# nguyenly.net
KiCad netlist of a schematic drawn in Altium Designer
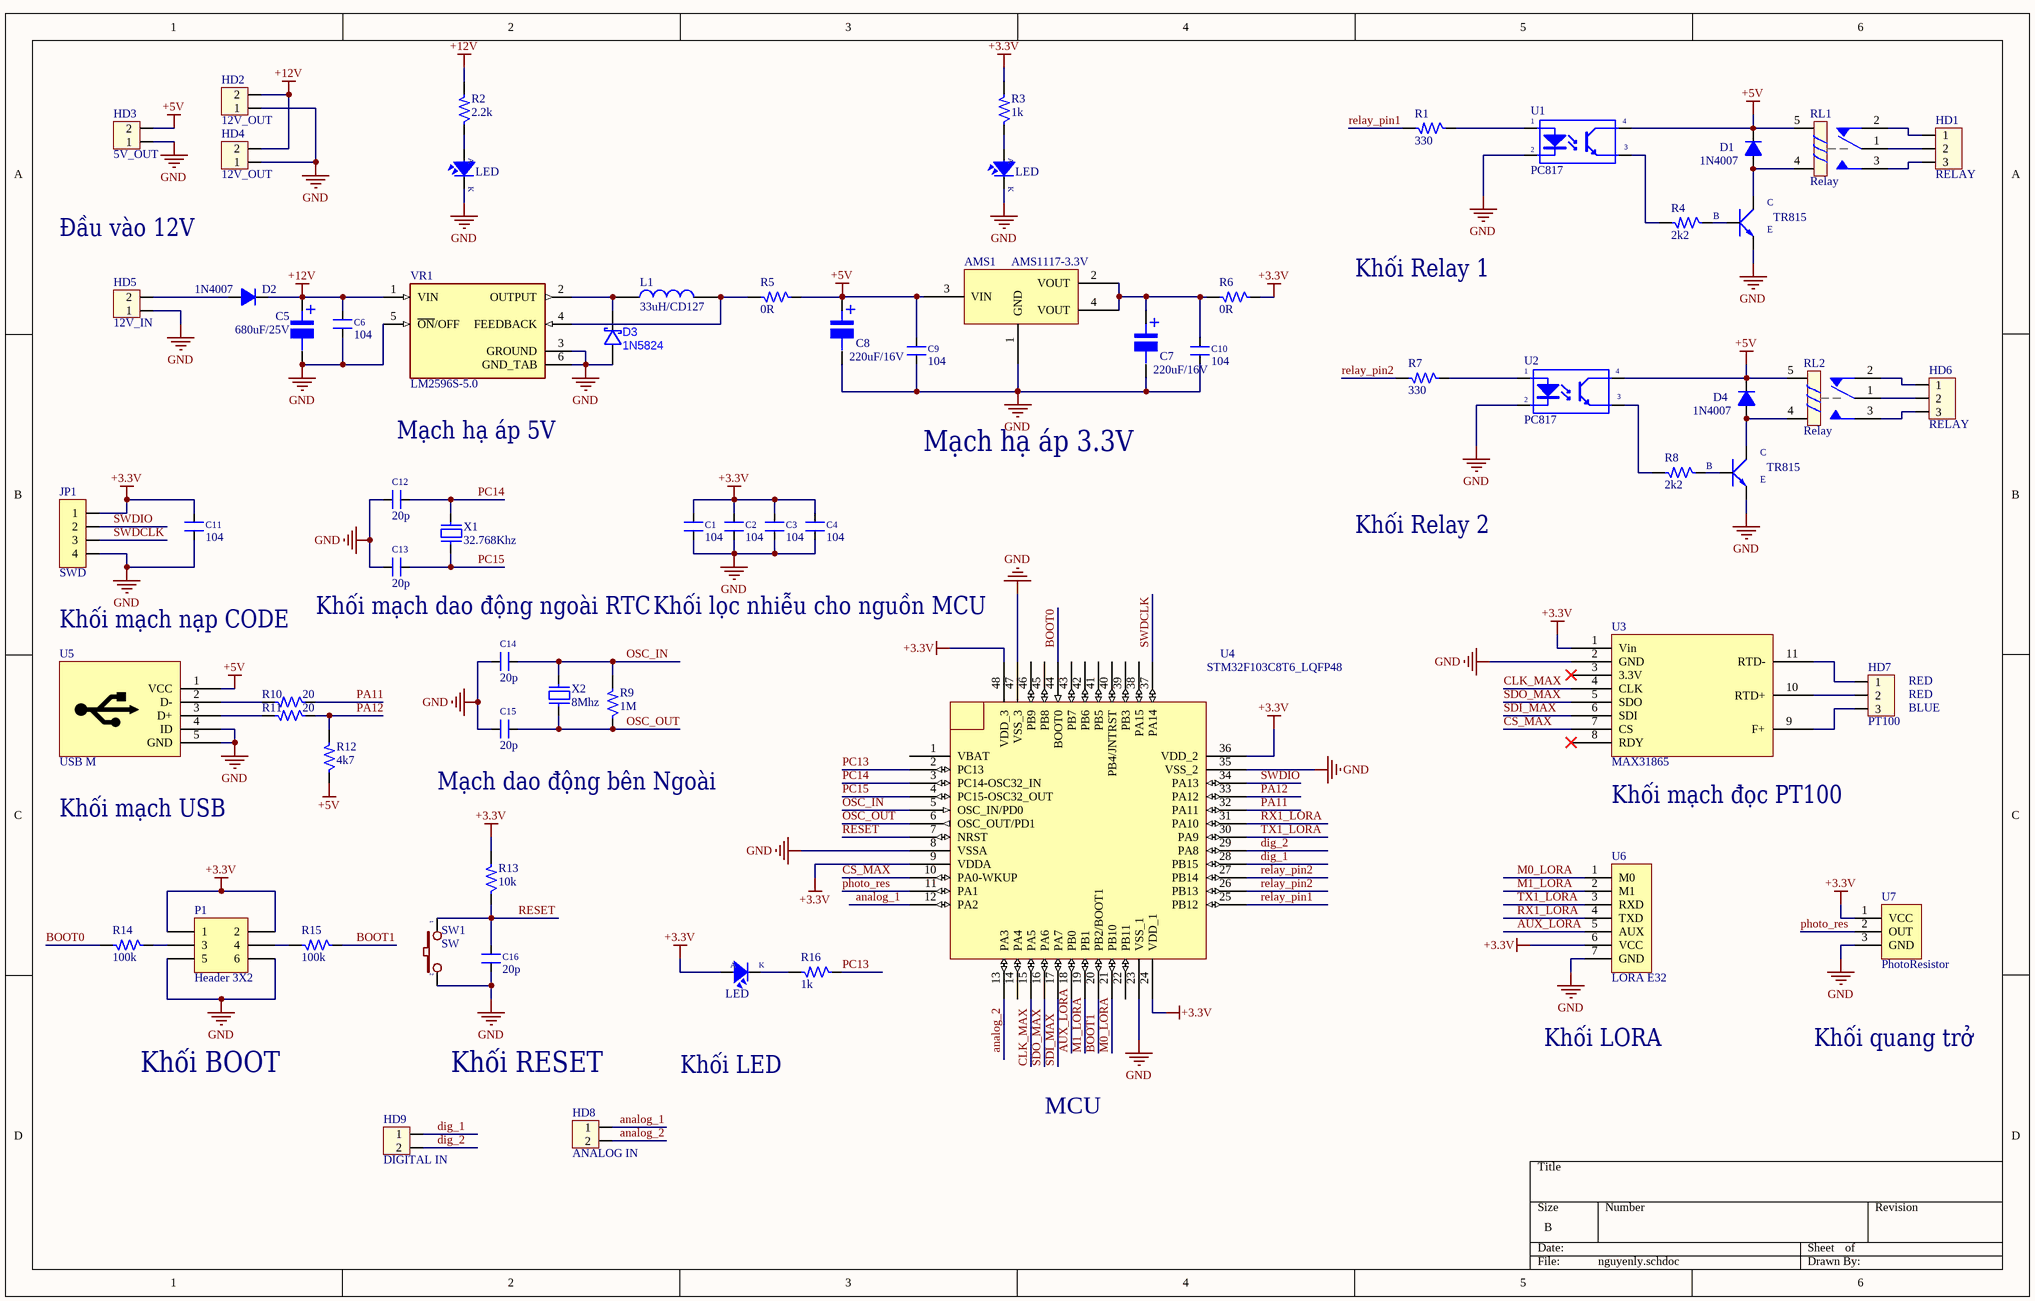
[diagram p0: nguyenly.schdoc]

(export (version "E")
  (design (tool "Eeschema 10.0.6"))
  (components
    (comp (ref "AMS1")
      (value "AMS1117-3.3V")
      (footprint "SOT223")
      (description "thegioiic. Dán (SOT-223)")
      (libsource (lib "Altium_Lib_by_KhueNguyenCreator") (part "AMS1117 SMD"))
    )
    (comp (ref "C1")
      (value "104")
      (footprint "SM-CAP-0805")
      (fields (field (name "DESIGNED BY") "VanDungEvn"))
      (libsource (lib "My library altium") (part "CAP SMD"))
    )
    (comp (ref "C2")
      (value "104")
      (footprint "SM-CAP-0805")
      (fields (field (name "DESIGNED BY") "VanDungEvn"))
      (libsource (lib "My library altium") (part "CAP SMD"))
    )
    (comp (ref "C3")
      (value "104")
      (footprint "SM-CAP-0805")
      (fields (field (name "DESIGNED BY") "VanDungEvn"))
      (libsource (lib "My library altium") (part "CAP SMD"))
    )
    (comp (ref "C4")
      (value "104")
      (footprint "SM-CAP-0805")
      (fields (field (name "DESIGNED BY") "VanDungEvn"))
      (libsource (lib "My library altium") (part "CAP SMD"))
    )
    (comp (ref "C5")
      (value "680uF/25V")
      (footprint "tu nhom 10 (G)")
      (description "Dán. Mua ở thegioiic")
      (libsource (lib "Altium_Lib_by_KhueNguyenCreator") (part "Tu Nhom 220uF 25V"))
    )
    (comp (ref "C6")
      (value "104")
      (footprint "SM-CAP-0805")
      (fields (field (name "DESIGNED BY") "VanDungEvn"))
      (libsource (lib "My library altium") (part "CAP SMD"))
    )
    (comp (ref "C7")
      (value "220uF/16V")
      (footprint "tu nhom 6.3 (d)")
      (description "Dán. Mua ở thegioiic")
      (libsource (lib "Altium_Lib_by_KhueNguyenCreator") (part "Tu Nhom 220uF 25V"))
    )
    (comp (ref "C8")
      (value "220uF/16V")
      (footprint "tu nhom 6.3 (d)")
      (description "Dán. Mua ở thegioiic")
      (libsource (lib "Altium_Lib_by_KhueNguyenCreator") (part "Tu Nhom 220uF 25V"))
    )
    (comp (ref "C9")
      (value "104")
      (footprint "SM-CAP-0805")
      (fields (field (name "DESIGNED BY") "VanDungEvn"))
      (libsource (lib "My library altium") (part "CAP SMD"))
    )
    (comp (ref "C10")
      (value "104")
      (footprint "SM-CAP-0805")
      (fields (field (name "DESIGNED BY") "VanDungEvn"))
      (libsource (lib "My library altium") (part "CAP SMD"))
    )
    (comp (ref "C11")
      (value "104")
      (footprint "SM-CAP-0805")
      (fields (field (name "DESIGNED BY") "VanDungEvn"))
      (libsource (lib "My library altium") (part "CAP SMD"))
    )
    (comp (ref "C12")
      (value "20p")
      (footprint "SM-CAP-0805")
      (fields (field (name "DESIGNED BY") "VanDungEvn"))
      (libsource (lib "My library altium") (part "CAP SMD"))
    )
    (comp (ref "C13")
      (value "20p")
      (footprint "SM-CAP-0805")
      (fields (field (name "DESIGNED BY") "VanDungEvn"))
      (libsource (lib "My library altium") (part "CAP SMD"))
    )
    (comp (ref "C14")
      (value "20p")
      (footprint "SM-CAP-0805")
      (fields (field (name "DESIGNED BY") "VanDungEvn"))
      (libsource (lib "My library altium") (part "CAP SMD"))
    )
    (comp (ref "C15")
      (value "20p")
      (footprint "SM-CAP-0805")
      (fields (field (name "DESIGNED BY") "VanDungEvn"))
      (libsource (lib "My library altium") (part "CAP SMD"))
    )
    (comp (ref "C16")
      (value "20p")
      (footprint "SM-CAP-0805")
      (fields (field (name "DESIGNED BY") "VanDungEvn"))
      (libsource (lib "My library altium") (part "CAP SMD"))
    )
    (comp (ref "D1")
      (value "1N4007")
      (footprint "DO-214AC")
      (description "Diode 1A")
      (libsource (lib "My library altium") (part "Diode  1N4007"))
    )
    (comp (ref "D2")
      (value "1N4007")
      (footprint "DO-214AC")
      (description "Diode 1A")
      (libsource (lib "My library altium") (part "Diode  1N4007"))
    )
    (comp (ref "D3")
      (value "1N5824")
      (footprint "DO-214AA")
      (description "Diode Schottky SMD 30V 2A DO-214AA")
      (libsource (lib "My library altium") (part "DIODE_SCHOTTKY_MBRS130L"))
    )
    (comp (ref "D4")
      (value "1N4007")
      (footprint "DO-214AC")
      (description "Diode 1A")
      (libsource (lib "My library altium") (part "Diode  1N4007"))
    )
    (comp (ref "HD1")
      (value "RELAY")
      (footprint "HED3T")
      (description "Header 3 (Green)")
      (libsource (lib "My library altium") (part "Header 3"))
    )
    (comp (ref "HD2")
      (value "12V_OUT")
      (footprint "HED2T")
      (description "Header 2 (Green)")
      (libsource (lib "") (part "Header 2_1"))
    )
    (comp (ref "HD3")
      (value "5V_OUT")
      (footprint "HED2T")
      (description "Header 2 (Green)")
      (libsource (lib "") (part "Header 2_1"))
    )
    (comp (ref "HD4")
      (value "12V_OUT")
      (footprint "HED2T")
      (description "Header 2 (Green)")
      (libsource (lib "") (part "Header 2_1"))
    )
    (comp (ref "HD5")
      (value "12V_IN")
      (footprint "HED2T")
      (description "Header 2 (Green)")
      (libsource (lib "") (part "Header 2_1"))
    )
    (comp (ref "HD6")
      (value "RELAY")
      (footprint "HED3T")
      (description "Header 3 (Green)")
      (libsource (lib "My library altium") (part "Header 3"))
    )
    (comp (ref "HD7")
      (value "PT100")
      (footprint "HED3T")
      (description "Header 3 (Green)")
      (libsource (lib "My library altium") (part "Header 3"))
    )
    (comp (ref "HD8")
      (value "ANALOG IN")
      (footprint "HED2T")
      (description "Header 2 (Green)")
      (libsource (lib "My library altium") (part "Header 2"))
    )
    (comp (ref "HD9")
      (value "DIGITAL IN")
      (footprint "HED2T")
      (description "Header 2 (Green)")
      (libsource (lib "My library altium") (part "Header 2"))
    )
    (comp (ref "JP1")
      (value "SWD")
      (footprint "JP 1x4 DT")
      (description "Cắm")
      (libsource (lib "Altium_Lib_by_KhueNguyenCreator") (part "JP 1x4 2.54 Duc Thang"))
    )
    (comp (ref "L1")
      (value "33uH/CD127")
      (footprint "SRR1208")
      (description "Inductor")
      (libsource (lib "My library altium") (part "Inductor Iron"))
    )
    (comp (ref "LED1")
      (value "LED")
      (footprint "LED-0805-Red")
      (description "LED RED 0805")
      (libsource (lib "My library altium") (part "LED"))
    )
    (comp (ref "LED2")
      (value "LED")
      (footprint "LED-0805-Red")
      (description "LED RED 0805")
      (libsource (lib "My library altium") (part "LED"))
    )
    (comp (ref "LED3")
      (value "LED")
      (footprint "LED-0805-Red")
      (description "LED RED 0805")
      (libsource (lib "My library altium") (part "LED"))
    )
    (comp (ref "P1")
      (value "Header 3X2")
      (footprint "HDR2X3")
      (description "Header, 3-Pin, Dual row")
      (fields (field (name "PUBLISHER") "Altium Limited"))
      (libsource (lib "My library altium") (part "Header 3X2"))
    )
    (comp (ref "R1")
      (value "330")
      (footprint "RES-SMD-0805")
      (description "Res SMD 0805")
      (libsource (lib "My library altium") (part "Res"))
    )
    (comp (ref "R2")
      (value "2.2k")
      (footprint "RES-SMD-0805")
      (description "Res SMD 0805")
      (libsource (lib "My library altium") (part "Res"))
    )
    (comp (ref "R3")
      (value "1k")
      (footprint "RES-SMD-0805")
      (description "Res SMD 0805")
      (libsource (lib "My library altium") (part "Res"))
    )
    (comp (ref "R4")
      (value "2k2")
      (footprint "RES-SMD-0805")
      (description "Res SMD 0805")
      (libsource (lib "My library altium") (part "Res"))
    )
    (comp (ref "R5")
      (value "0R")
      (footprint "RES-SMD-0805")
      (description "Res SMD 0805")
      (libsource (lib "My library altium") (part "Res"))
    )
    (comp (ref "R6")
      (value "0R")
      (footprint "RES-SMD-0805")
      (description "Res SMD 0805")
      (libsource (lib "My library altium") (part "Res"))
    )
    (comp (ref "R7")
      (value "330")
      (footprint "RES-SMD-0805")
      (description "Res SMD 0805")
      (libsource (lib "My library altium") (part "Res"))
    )
    (comp (ref "R8")
      (value "2k2")
      (footprint "RES-SMD-0805")
      (description "Res SMD 0805")
      (libsource (lib "My library altium") (part "Res"))
    )
    (comp (ref "R9")
      (value "1M")
      (footprint "RES-SMD-0805")
      (description "Res SMD 0805")
      (libsource (lib "My library altium") (part "Res"))
    )
    (comp (ref "R10")
      (value "20")
      (footprint "RES-SMD-0805")
      (description "Res SMD 0805")
      (libsource (lib "My library altium") (part "Res"))
    )
    (comp (ref "R11")
      (value "20")
      (footprint "RES-SMD-0805")
      (description "Res SMD 0805")
      (libsource (lib "My library altium") (part "Res"))
    )
    (comp (ref "R12")
      (value "4k7")
      (footprint "RES-SMD-0805")
      (description "Res SMD 0805")
      (libsource (lib "My library altium") (part "Res"))
    )
    (comp (ref "R13")
      (value "10k")
      (footprint "RES-SMD-0805")
      (description "Res SMD 0805")
      (libsource (lib "My library altium") (part "Res"))
    )
    (comp (ref "R14")
      (value "100k")
      (footprint "RES-SMD-0805")
      (description "Res SMD 0805")
      (libsource (lib "My library altium") (part "Res"))
    )
    (comp (ref "R15")
      (value "100k")
      (footprint "RES-SMD-0805")
      (description "Res SMD 0805")
      (libsource (lib "My library altium") (part "Res"))
    )
    (comp (ref "R16")
      (value "1k")
      (footprint "RES-SMD-0805")
      (description "Res SMD 0805")
      (libsource (lib "My library altium") (part "Res"))
    )
    (comp (ref "RL1")
      (value "Relay")
      (footprint "RL_SPDT_10A")
      (description "Relay SPDT 5 Pin")
      (libsource (lib "My library altium") (part "Relay SRD"))
    )
    (comp (ref "RL2")
      (value "Relay")
      (footprint "RL_SPDT_10A")
      (description "Relay SPDT 5 Pin")
      (libsource (lib "My library altium") (part "Relay SRD"))
    )
    (comp (ref "STA.TR1")
      (value "TR815")
      (footprint "QTO-92")
      (description "NPN 600mW, ECB")
      (libsource (lib "My library altium") (part "C1815"))
    )
    (comp (ref "STA.TR2")
      (value "TR815")
      (footprint "QTO-92")
      (description "NPN 600mW, ECB")
      (libsource (lib "My library altium") (part "C1815"))
    )
    (comp (ref "SW1")
      (value "SW")
      (footprint "SW4 CMD M")
      (description "Switch button 2 pin")
      (libsource (lib "TechMT.VN_Lib_Project v2") (part "SW2"))
    )
    (comp (ref "U1")
      (value "PC817")
      (footprint "SOP4")
      (description "Single Opto")
      (libsource (lib "syhaunguyen") (part "PC817"))
    )
    (comp (ref "U2")
      (value "PC817")
      (footprint "SOP4")
      (description "Single Opto")
      (libsource (lib "syhaunguyen") (part "PC817"))
    )
    (comp (ref "U3")
      (value "MAX31865")
      (footprint "MAX31865_module")
      (libsource (lib "MAX31865") (part "MAX31865 Module"))
    )
    (comp (ref "U4")
      (value "STM32F103C8T6_LQFP48")
      (footprint "STM32_LQPF48")
      (description "STM32 ARM-based 32-bit MCU with 64 Kbytes Flash, 48-pin LQFP, Industrial Temperature")
      (fields (field (name "PUBLISHER") "Altium Limited"))
      (libsource (lib "My library altium") (part "STM32F103xx_LQFP48"))
    )
    (comp (ref "U5")
      (value "USB M")
      (footprint "USB_MICRO_B")
      (libsource (lib "My library altium") (part "USB M"))
    )
    (comp (ref "U6") (value "LORA E32") (footprint "LORA E32") (libsource (lib "SCH_LORA") (part "LORA E32")))
    (comp (ref "U7")
      (value "PhotoResistor")
      (footprint "PhotoResistor_module")
      (libsource (lib "PhotoRes") (part "PhotoResistor"))
    )
    (comp (ref "VR1")
      (value "LM2596S-5.0")
      (footprint "TO170P1524X483-6N")
      (description "thegioiic. Dán (TO-263-5)")
      (fields (field (name "MP") "LM2596S-5.0/NOPB") (field (name "MF") "Texas Instruments"))
      (libsource (lib "LM2596S-5.0") (part "LM2596S-5.0"))
    )
    (comp (ref "X1")
      (value "32.768Khz")
      (footprint "CRYSTAL 32,768 kHz")
      (description "Crystal 32.768Khz 9pF and 12pF")
      (libsource (lib "syhaunguyen") (part "XT2"))
    )
    (comp (ref "X2")
      (value "8Mhz")
      (footprint "XT2")
      (description "Crystal For all Crystal 2pin.")
      (libsource (lib "syhaunguyen") (part "XT2"))
    )
  )
  (nets
    (net (code "1") (name "+3.3V") (class "Default")
      (node (ref "C1") (pin "2") (pinfunction "2_2") (pintype "passive"))
      (node (ref "C11") (pin "2") (pinfunction "2_2") (pintype "passive"))
      (node (ref "C2") (pin "2") (pinfunction "2_2") (pintype "passive"))
      (node (ref "C3") (pin "2") (pinfunction "2_2") (pintype "passive"))
      (node (ref "C4") (pin "2") (pinfunction "2_2") (pintype "passive"))
      (node (ref "JP1") (pin "1") (pinfunction "1_1") (pintype "passive"))
      (node (ref "LED3") (pin "1") (pinfunction "A_1") (pintype "passive"))
      (node (ref "P1") (pin "1") (pinfunction "1_1") (pintype "passive"))
      (node (ref "P1") (pin "2") (pinfunction "2_2") (pintype "passive"))
      (node (ref "R13") (pin "2") (pinfunction "2_2") (pintype "passive"))
      (node (ref "R3") (pin "2") (pinfunction "2_2") (pintype "passive"))
      (node (ref "R6") (pin "1") (pinfunction "1_1") (pintype "passive"))
      (node (ref "U3") (pin "1") (pinfunction "Vin_1") (pintype "passive"))
      (node (ref "U4") (pin "24") (pinfunction "VDD_1_24") (pintype "power_in"))
      (node (ref "U4") (pin "36") (pinfunction "VDD_2_36") (pintype "power_in"))
      (node (ref "U4") (pin "48") (pinfunction "VDD_3_48") (pintype "power_in"))
      (node (ref "U4") (pin "9") (pinfunction "VDDA_9") (pintype "power_in"))
      (node (ref "U6") (pin "6") (pinfunction "VCC_6") (pintype "passive"))
      (node (ref "U7") (pin "1") (pinfunction "VCC_1") (pintype "passive"))
    )
    (net (code "2") (name "+5V") (class "Default")
      (node (ref "AMS1") (pin "3") (pinfunction "VIN_3") (pintype "passive"))
      (node (ref "C8") (pin "1") (pinfunction "1_1") (pintype "passive"))
      (node (ref "C9") (pin "2") (pinfunction "2_2") (pintype "passive"))
      (node (ref "D1") (pin "K") (pinfunction "K_K") (pintype "passive"))
      (node (ref "D4") (pin "K") (pinfunction "K_K") (pintype "passive"))
      (node (ref "HD3") (pin "2") (pinfunction "2_2") (pintype "passive"))
      (node (ref "R12") (pin "1") (pinfunction "1_1") (pintype "passive"))
      (node (ref "R5") (pin "1") (pinfunction "1_1") (pintype "passive"))
      (node (ref "RL1") (pin "5") (pinfunction "5_5") (pintype "passive"))
      (node (ref "RL2") (pin "5") (pinfunction "5_5") (pintype "passive"))
      (node (ref "U1") (pin "4") (pinfunction "C_4") (pintype "passive"))
      (node (ref "U2") (pin "4") (pinfunction "C_4") (pintype "passive"))
      (node (ref "U5") (pin "1") (pinfunction "VCC_1") (pintype "passive"))
    )
    (net (code "3") (name "+12V") (class "Default")
      (node (ref "C5") (pin "1") (pinfunction "1_1") (pintype "passive"))
      (node (ref "C6") (pin "2") (pinfunction "2_2") (pintype "passive"))
      (node (ref "D2") (pin "K") (pinfunction "K_K") (pintype "passive"))
      (node (ref "HD2") (pin "2") (pinfunction "2_2") (pintype "passive"))
      (node (ref "HD4") (pin "2") (pinfunction "2_2") (pintype "passive"))
      (node (ref "R2") (pin "2") (pinfunction "2_2") (pintype "passive"))
      (node (ref "VR1") (pin "1") (pinfunction "VIN_1") (pintype "input"))
    )
    (net (code "4") (name "/AUX_LORA") (class "Default")
      (node (ref "U4") (pin "18") (pinfunction "PB0_18") (pintype "bidirectional"))
      (node (ref "U6") (pin "5") (pinfunction "AUX_5") (pintype "passive"))
    )
    (net (code "5") (name "/BOOT0") (class "Default")
      (node (ref "R14") (pin "2") (pinfunction "2_2") (pintype "passive"))
      (node (ref "U4") (pin "44") (pinfunction "BOOT0_44") (pintype "input"))
    )
    (net (code "6") (name "/BOOT1") (class "Default")
      (node (ref "R15") (pin "1") (pinfunction "1_1") (pintype "passive"))
      (node (ref "U4") (pin "20") (pinfunction "PB2/BOOT1_20") (pintype "bidirectional"))
    )
    (net (code "7") (name "/CLK_MAX") (class "Default")
      (node (ref "U3") (pin "4") (pinfunction "CLK_4") (pintype "passive"))
      (node (ref "U4") (pin "15") (pinfunction "PA5_15") (pintype "bidirectional"))
    )
    (net (code "8") (name "/CS_MAX") (class "Default")
      (node (ref "U3") (pin "7") (pinfunction "CS_7") (pintype "passive"))
      (node (ref "U4") (pin "10") (pinfunction "PA0-WKUP_10") (pintype "bidirectional"))
    )
    (net (code "9") (name "/M0_LORA") (class "Default")
      (node (ref "U4") (pin "21") (pinfunction "PB10_21") (pintype "bidirectional"))
      (node (ref "U6") (pin "1") (pinfunction "M0_1") (pintype "passive"))
    )
    (net (code "10") (name "/M1_LORA") (class "Default")
      (node (ref "U4") (pin "19") (pinfunction "PB1_19") (pintype "bidirectional"))
      (node (ref "U6") (pin "2") (pinfunction "M1_2") (pintype "passive"))
    )
    (net (code "11") (name "/OSC_IN") (class "Default")
      (node (ref "C14") (pin "1") (pinfunction "1_1") (pintype "passive"))
      (node (ref "R9") (pin "2") (pinfunction "2_2") (pintype "passive"))
      (node (ref "U4") (pin "5") (pinfunction "OSC_IN/PD0_5") (pintype "input"))
      (node (ref "X2") (pin "2") (pinfunction "2_2") (pintype "passive"))
    )
    (net (code "12") (name "/OSC_OUT") (class "Default")
      (node (ref "C15") (pin "1") (pinfunction "1_1") (pintype "passive"))
      (node (ref "R9") (pin "1") (pinfunction "1_1") (pintype "passive"))
      (node (ref "U4") (pin "6") (pinfunction "OSC_OUT/PD1_6") (pintype "output"))
      (node (ref "X2") (pin "1") (pinfunction "1_1") (pintype "passive"))
    )
    (net (code "13") (name "/PA11") (class "Default")
      (node (ref "R10") (pin "1") (pinfunction "1_1") (pintype "passive"))
      (node (ref "U4") (pin "32") (pinfunction "PA11_32") (pintype "bidirectional"))
    )
    (net (code "14") (name "/PA12") (class "Default")
      (node (ref "R11") (pin "1") (pinfunction "1_1") (pintype "passive"))
      (node (ref "R12") (pin "2") (pinfunction "2_2") (pintype "passive"))
      (node (ref "U4") (pin "33") (pinfunction "PA12_33") (pintype "bidirectional"))
    )
    (net (code "15") (name "/PC13") (class "Default")
      (node (ref "R16") (pin "1") (pinfunction "1_1") (pintype "passive"))
      (node (ref "U4") (pin "2") (pinfunction "PC13_2") (pintype "bidirectional"))
    )
    (net (code "16") (name "/PC14") (class "Default")
      (node (ref "C12") (pin "1") (pinfunction "1_1") (pintype "passive"))
      (node (ref "U4") (pin "3") (pinfunction "PC14-OSC32_IN_3") (pintype "bidirectional"))
      (node (ref "X1") (pin "2") (pinfunction "2_2") (pintype "passive"))
    )
    (net (code "17") (name "/PC15") (class "Default")
      (node (ref "C13") (pin "1") (pinfunction "1_1") (pintype "passive"))
      (node (ref "U4") (pin "4") (pinfunction "PC15-OSC32_OUT_4") (pintype "bidirectional"))
      (node (ref "X1") (pin "1") (pinfunction "1_1") (pintype "passive"))
    )
    (net (code "18") (name "/RESET") (class "Default")
      (node (ref "C16") (pin "1") (pinfunction "1_1") (pintype "passive"))
      (node (ref "R13") (pin "1") (pinfunction "1_1") (pintype "passive"))
      (node (ref "SW1") (pin "1") (pinfunction "1_1") (pintype "passive"))
      (node (ref "U4") (pin "7") (pinfunction "NRST_7") (pintype "bidirectional"))
    )
    (net (code "19") (name "/RX1_LORA") (class "Default")
      (node (ref "U4") (pin "31") (pinfunction "PA10_31") (pintype "bidirectional"))
      (node (ref "U6") (pin "4") (pinfunction "TXD_4") (pintype "passive"))
    )
    (net (code "20") (name "/SDI_MAX") (class "Default")
      (node (ref "U3") (pin "6") (pinfunction "SDI_6") (pintype "passive"))
      (node (ref "U4") (pin "17") (pinfunction "PA7_17") (pintype "bidirectional"))
    )
    (net (code "21") (name "/SDO_MAX") (class "Default")
      (node (ref "U3") (pin "5") (pinfunction "SDO_5") (pintype "passive"))
      (node (ref "U4") (pin "16") (pinfunction "PA6_16") (pintype "bidirectional"))
    )
    (net (code "22") (name "/SWDCLK") (class "Default")
      (node (ref "JP1") (pin "3") (pinfunction "3_3") (pintype "passive"))
      (node (ref "U4") (pin "37") (pinfunction "PA14_37") (pintype "bidirectional"))
    )
    (net (code "23") (name "/SWDIO") (class "Default")
      (node (ref "JP1") (pin "2") (pinfunction "2_2") (pintype "passive"))
      (node (ref "U4") (pin "34") (pinfunction "PA13_34") (pintype "bidirectional"))
    )
    (net (code "24") (name "/TX1_LORA") (class "Default")
      (node (ref "U4") (pin "30") (pinfunction "PA9_30") (pintype "bidirectional"))
      (node (ref "U6") (pin "3") (pinfunction "RXD_3") (pintype "passive"))
    )
    (net (code "25") (name "/analog_1") (class "Default")
      (node (ref "HD8") (pin "1") (pinfunction "1_1") (pintype "passive"))
      (node (ref "U4") (pin "12") (pinfunction "PA2_12") (pintype "bidirectional"))
    )
    (net (code "26") (name "/analog_2") (class "Default")
      (node (ref "HD8") (pin "2") (pinfunction "2_2") (pintype "passive"))
      (node (ref "U4") (pin "13") (pinfunction "PA3_13") (pintype "bidirectional"))
    )
    (net (code "27") (name "/dig_1") (class "Default")
      (node (ref "HD9") (pin "1") (pinfunction "1_1") (pintype "passive"))
      (node (ref "U4") (pin "28") (pinfunction "PB15_28") (pintype "bidirectional"))
    )
    (net (code "28") (name "/dig_2") (class "Default")
      (node (ref "HD9") (pin "2") (pinfunction "2_2") (pintype "passive"))
      (node (ref "U4") (pin "29") (pinfunction "PA8_29") (pintype "bidirectional"))
    )
    (net (code "29") (name "/photo_res") (class "Default")
      (node (ref "U4") (pin "11") (pinfunction "PA1_11") (pintype "bidirectional"))
      (node (ref "U7") (pin "2") (pinfunction "OUT_2") (pintype "passive"))
    )
    (net (code "30") (name "/relay_pin1") (class "Default")
      (node (ref "R1") (pin "2") (pinfunction "2_2") (pintype "passive"))
      (node (ref "U4") (pin "25") (pinfunction "PB12_25") (pintype "bidirectional"))
    )
    (net (code "31") (name "/relay_pin2") (class "Default")
      (node (ref "R7") (pin "2") (pinfunction "2_2") (pintype "passive"))
      (node (ref "U4") (pin "26") (pinfunction "PB13_26") (pintype "bidirectional"))
      (node (ref "U4") (pin "27") (pinfunction "PB14_27") (pintype "bidirectional"))
    )
    (net (code "32") (name "GND") (class "Default")
      (node (ref "AMS1") (pin "1") (pinfunction "GND_1") (pintype "passive"))
      (node (ref "C1") (pin "1") (pinfunction "1_1") (pintype "passive"))
      (node (ref "C10") (pin "1") (pinfunction "1_1") (pintype "passive"))
      (node (ref "C11") (pin "1") (pinfunction "1_1") (pintype "passive"))
      (node (ref "C12") (pin "2") (pinfunction "2_2") (pintype "passive"))
      (node (ref "C13") (pin "2") (pinfunction "2_2") (pintype "passive"))
      (node (ref "C14") (pin "2") (pinfunction "2_2") (pintype "passive"))
      (node (ref "C15") (pin "2") (pinfunction "2_2") (pintype "passive"))
      (node (ref "C16") (pin "2") (pinfunction "2_2") (pintype "passive"))
      (node (ref "C2") (pin "1") (pinfunction "1_1") (pintype "passive"))
      (node (ref "C3") (pin "1") (pinfunction "1_1") (pintype "passive"))
      (node (ref "C4") (pin "1") (pinfunction "1_1") (pintype "passive"))
      (node (ref "C5") (pin "2") (pinfunction "2_2") (pintype "passive"))
      (node (ref "C6") (pin "1") (pinfunction "1_1") (pintype "passive"))
      (node (ref "C7") (pin "2") (pinfunction "2_2") (pintype "passive"))
      (node (ref "C8") (pin "2") (pinfunction "2_2") (pintype "passive"))
      (node (ref "C9") (pin "1") (pinfunction "1_1") (pintype "passive"))
      (node (ref "D3") (pin "A") (pinfunction "A_A") (pintype "passive"))
      (node (ref "HD2") (pin "1") (pinfunction "1_1") (pintype "passive"))
      (node (ref "HD3") (pin "1") (pinfunction "1_1") (pintype "passive"))
      (node (ref "HD4") (pin "1") (pinfunction "1_1") (pintype "passive"))
      (node (ref "HD5") (pin "1") (pinfunction "1_1") (pintype "passive"))
      (node (ref "JP1") (pin "4") (pinfunction "4_4") (pintype "passive"))
      (node (ref "LED1") (pin "2") (pinfunction "K_2") (pintype "passive"))
      (node (ref "LED2") (pin "2") (pinfunction "K_2") (pintype "passive"))
      (node (ref "P1") (pin "5") (pinfunction "5_5") (pintype "passive"))
      (node (ref "P1") (pin "6") (pinfunction "6_6") (pintype "passive"))
      (node (ref "STA.TR1") (pin "1") (pinfunction "E_1") (pintype "passive"))
      (node (ref "STA.TR2") (pin "1") (pinfunction "E_1") (pintype "passive"))
      (node (ref "SW1") (pin "2") (pinfunction "2_2") (pintype "passive"))
      (node (ref "U1") (pin "2") (pinfunction "K_2") (pintype "passive"))
      (node (ref "U2") (pin "2") (pinfunction "K_2") (pintype "passive"))
      (node (ref "U3") (pin "2") (pinfunction "GND_2") (pintype "passive"))
      (node (ref "U4") (pin "23") (pinfunction "VSS_1_23") (pintype "power_in"))
      (node (ref "U4") (pin "35") (pinfunction "VSS_2_35") (pintype "power_in"))
      (node (ref "U4") (pin "47") (pinfunction "VSS_3_47") (pintype "power_in"))
      (node (ref "U4") (pin "8") (pinfunction "VSSA_8") (pintype "power_in"))
      (node (ref "U5") (pin "4") (pinfunction "ID_4") (pintype "passive"))
      (node (ref "U5") (pin "5") (pinfunction "GND_5") (pintype "passive"))
      (node (ref "U6") (pin "7") (pinfunction "GND_7") (pintype "passive"))
      (node (ref "U7") (pin "3") (pinfunction "GND_3") (pintype "passive"))
      (node (ref "VR1") (pin "3") (pinfunction "GROUND_3") (pintype "power_in"))
      (node (ref "VR1") (pin "5") (pinfunction "~{ON}/OFF_5") (pintype "input"))
      (node (ref "VR1") (pin "6") (pinfunction "GND_TAB_6") (pintype "power_in"))
    )
    (net (code "33") (name "Net-(AMS1-VOUT-Pad2)") (class "Default")
      (node (ref "AMS1") (pin "2") (pinfunction "VOUT_2") (pintype "passive"))
      (node (ref "AMS1") (pin "4") (pinfunction "VOUT_4") (pintype "passive"))
      (node (ref "C10") (pin "2") (pinfunction "2_2") (pintype "passive"))
      (node (ref "C7") (pin "1") (pinfunction "1_1") (pintype "passive"))
      (node (ref "R6") (pin "2") (pinfunction "2_2") (pintype "passive"))
    )
    (net (code "34") (name "Net-(D2-PadA)") (class "Default")
      (node (ref "D2") (pin "A") (pinfunction "A_A") (pintype "passive"))
      (node (ref "HD5") (pin "2") (pinfunction "2_2") (pintype "passive"))
    )
    (net (code "35") (name "Net-(HD1-Pad1)") (class "Default")
      (node (ref "HD1") (pin "1") (pinfunction "1_1") (pintype "passive"))
      (node (ref "RL1") (pin "2") (pinfunction "2_2") (pintype "passive"))
    )
    (net (code "36") (name "Net-(HD1-Pad2)") (class "Default")
      (node (ref "HD1") (pin "2") (pinfunction "2_2") (pintype "passive"))
      (node (ref "RL1") (pin "1") (pinfunction "1_1") (pintype "passive"))
    )
    (net (code "37") (name "Net-(HD1-Pad3)") (class "Default")
      (node (ref "HD1") (pin "3") (pinfunction "3_3") (pintype "passive"))
      (node (ref "RL1") (pin "3") (pinfunction "3_3") (pintype "passive"))
    )
    (net (code "38") (name "Net-(HD6-Pad1)") (class "Default")
      (node (ref "HD6") (pin "1") (pinfunction "1_1") (pintype "passive"))
      (node (ref "RL2") (pin "2") (pinfunction "2_2") (pintype "passive"))
    )
    (net (code "39") (name "Net-(HD6-Pad2)") (class "Default")
      (node (ref "HD6") (pin "2") (pinfunction "2_2") (pintype "passive"))
      (node (ref "RL2") (pin "1") (pinfunction "1_1") (pintype "passive"))
    )
    (net (code "40") (name "Net-(HD6-Pad3)") (class "Default")
      (node (ref "HD6") (pin "3") (pinfunction "3_3") (pintype "passive"))
      (node (ref "RL2") (pin "3") (pinfunction "3_3") (pintype "passive"))
    )
    (net (code "41") (name "Net-(LED1-A)") (class "Default")
      (node (ref "LED1") (pin "1") (pinfunction "A_1") (pintype "passive"))
      (node (ref "R2") (pin "1") (pinfunction "1_1") (pintype "passive"))
    )
    (net (code "42") (name "Net-(LED2-A)") (class "Default")
      (node (ref "LED2") (pin "1") (pinfunction "A_1") (pintype "passive"))
      (node (ref "R3") (pin "1") (pinfunction "1_1") (pintype "passive"))
    )
    (net (code "43") (name "Net-(LED3-K)") (class "Default")
      (node (ref "LED3") (pin "2") (pinfunction "K_2") (pintype "passive"))
      (node (ref "R16") (pin "2") (pinfunction "2_2") (pintype "passive"))
    )
    (net (code "44") (name "Net-(P1-Pad3)") (class "Default")
      (node (ref "P1") (pin "3") (pinfunction "3_3") (pintype "passive"))
      (node (ref "R14") (pin "1") (pinfunction "1_1") (pintype "passive"))
    )
    (net (code "45") (name "Net-(P1-Pad4)") (class "Default")
      (node (ref "P1") (pin "4") (pinfunction "4_4") (pintype "passive"))
      (node (ref "R15") (pin "2") (pinfunction "2_2") (pintype "passive"))
    )
    (net (code "46") (name "Net-(STA.TR1-B)") (class "Default")
      (node (ref "R4") (pin "1") (pinfunction "1_1") (pintype "passive"))
      (node (ref "STA.TR1") (pin "3") (pinfunction "B_3") (pintype "passive"))
    )
    (net (code "47") (name "Net-(STA.TR1-C)") (class "Default")
      (node (ref "D1") (pin "A") (pinfunction "A_A") (pintype "passive"))
      (node (ref "RL1") (pin "4") (pinfunction "4_4") (pintype "passive"))
      (node (ref "STA.TR1") (pin "2") (pinfunction "C_2") (pintype "passive"))
    )
    (net (code "48") (name "Net-(STA.TR2-B)") (class "Default")
      (node (ref "R8") (pin "1") (pinfunction "1_1") (pintype "passive"))
      (node (ref "STA.TR2") (pin "3") (pinfunction "B_3") (pintype "passive"))
    )
    (net (code "49") (name "Net-(STA.TR2-C)") (class "Default")
      (node (ref "D4") (pin "A") (pinfunction "A_A") (pintype "passive"))
      (node (ref "RL2") (pin "4") (pinfunction "4_4") (pintype "passive"))
      (node (ref "STA.TR2") (pin "2") (pinfunction "C_2") (pintype "passive"))
    )
    (net (code "50") (name "Net-(U1-A)") (class "Default")
      (node (ref "R1") (pin "1") (pinfunction "1_1") (pintype "passive"))
      (node (ref "U1") (pin "1") (pinfunction "A_1") (pintype "passive"))
    )
    (net (code "51") (name "Net-(U1-E)") (class "Default")
      (node (ref "R4") (pin "2") (pinfunction "2_2") (pintype "passive"))
      (node (ref "U1") (pin "3") (pinfunction "E_3") (pintype "passive"))
    )
    (net (code "52") (name "Net-(U2-A)") (class "Default")
      (node (ref "R7") (pin "1") (pinfunction "1_1") (pintype "passive"))
      (node (ref "U2") (pin "1") (pinfunction "A_1") (pintype "passive"))
    )
    (net (code "53") (name "Net-(U2-E)") (class "Default")
      (node (ref "R8") (pin "2") (pinfunction "2_2") (pintype "passive"))
      (node (ref "U2") (pin "3") (pinfunction "E_3") (pintype "passive"))
    )
    (net (code "54") (name "Net-(U3-F+)") (class "Default")
      (node (ref "HD7") (pin "3") (pinfunction "3_3") (pintype "passive"))
      (node (ref "U3") (pin "9") (pinfunction "F+_9") (pintype "passive"))
    )
    (net (code "55") (name "Net-(U3-RTD+)") (class "Default")
      (node (ref "HD7") (pin "2") (pinfunction "2_2") (pintype "passive"))
      (node (ref "U3") (pin "10") (pinfunction "RTD+_10") (pintype "passive"))
    )
    (net (code "56") (name "Net-(U3-RTD-)") (class "Default")
      (node (ref "HD7") (pin "1") (pinfunction "1_1") (pintype "passive"))
      (node (ref "U3") (pin "11") (pinfunction "RTD-_11") (pintype "passive"))
    )
    (net (code "57") (name "Net-(U5-D+)") (class "Default")
      (node (ref "R11") (pin "2") (pinfunction "2_2") (pintype "passive"))
      (node (ref "U5") (pin "3") (pinfunction "D+_3") (pintype "passive"))
    )
    (net (code "58") (name "Net-(U5-D-)") (class "Default")
      (node (ref "R10") (pin "2") (pinfunction "2_2") (pintype "passive"))
      (node (ref "U5") (pin "2") (pinfunction "D-_2") (pintype "passive"))
    )
    (net (code "59") (name "Net-(VR1-FEEDBACK)") (class "Default")
      (node (ref "L1") (pin "2") (pinfunction "2_2") (pintype "passive"))
      (node (ref "R5") (pin "2") (pinfunction "2_2") (pintype "passive"))
      (node (ref "VR1") (pin "4") (pinfunction "FEEDBACK_4") (pintype "input"))
    )
    (net (code "60") (name "Net-(VR1-OUTPUT)") (class "Default")
      (node (ref "D3") (pin "K") (pinfunction "K_K") (pintype "passive"))
      (node (ref "L1") (pin "1") (pinfunction "1_1") (pintype "passive"))
      (node (ref "VR1") (pin "2") (pinfunction "OUTPUT_2") (pintype "output"))
    )
    (net (code "61") (name "unconnected-(U3-3.3V-Pad3)") (class "Default")
      (node (ref "U3") (pin "3") (pinfunction "3.3V_3") (pintype "passive+no_connect"))
    )
    (net (code "62") (name "unconnected-(U3-RDY-Pad8)") (class "Default")
      (node (ref "U3") (pin "8") (pinfunction "RDY_8") (pintype "passive+no_connect"))
    )
    (net (code "63") (name "unconnected-(U4-PA4-Pad14)") (class "Default")
      (node (ref "U4") (pin "14") (pinfunction "PA4_14") (pintype "bidirectional"))
    )
    (net (code "64") (name "unconnected-(U4-PA15-Pad38)") (class "Default")
      (node (ref "U4") (pin "38") (pinfunction "PA15_38") (pintype "bidirectional"))
    )
    (net (code "65") (name "unconnected-(U4-PB3-Pad39)") (class "Default")
      (node (ref "U4") (pin "39") (pinfunction "PB3_39") (pintype "bidirectional"))
    )
    (net (code "66") (name "unconnected-(U4-PB4{slash}JNTRST-Pad40)") (class "Default")
      (node (ref "U4") (pin "40") (pinfunction "PB4/JNTRST_40") (pintype "bidirectional"))
    )
    (net (code "67") (name "unconnected-(U4-PB5-Pad41)") (class "Default")
      (node (ref "U4") (pin "41") (pinfunction "PB5_41") (pintype "bidirectional"))
    )
    (net (code "68") (name "unconnected-(U4-PB6-Pad42)") (class "Default")
      (node (ref "U4") (pin "42") (pinfunction "PB6_42") (pintype "bidirectional"))
    )
    (net (code "69") (name "unconnected-(U4-PB7-Pad43)") (class "Default")
      (node (ref "U4") (pin "43") (pinfunction "PB7_43") (pintype "bidirectional"))
    )
    (net (code "70") (name "unconnected-(U4-PB8-Pad45)") (class "Default")
      (node (ref "U4") (pin "45") (pinfunction "PB8_45") (pintype "bidirectional"))
    )
    (net (code "71") (name "unconnected-(U4-PB9-Pad46)") (class "Default")
      (node (ref "U4") (pin "46") (pinfunction "PB9_46") (pintype "bidirectional"))
    )
    (net (code "72") (name "unconnected-(U4-PB11-Pad22)") (class "Default")
      (node (ref "U4") (pin "22") (pinfunction "PB11_22") (pintype "bidirectional"))
    )
    (net (code "73") (name "unconnected-(U4-VBAT-Pad1)") (class "Default")
      (node (ref "U4") (pin "1") (pinfunction "VBAT_1") (pintype "power_in"))
    )
  )
)
